# Qwiic_Featherwing.net
KiCad netlist of a schematic drawn in EAGLE
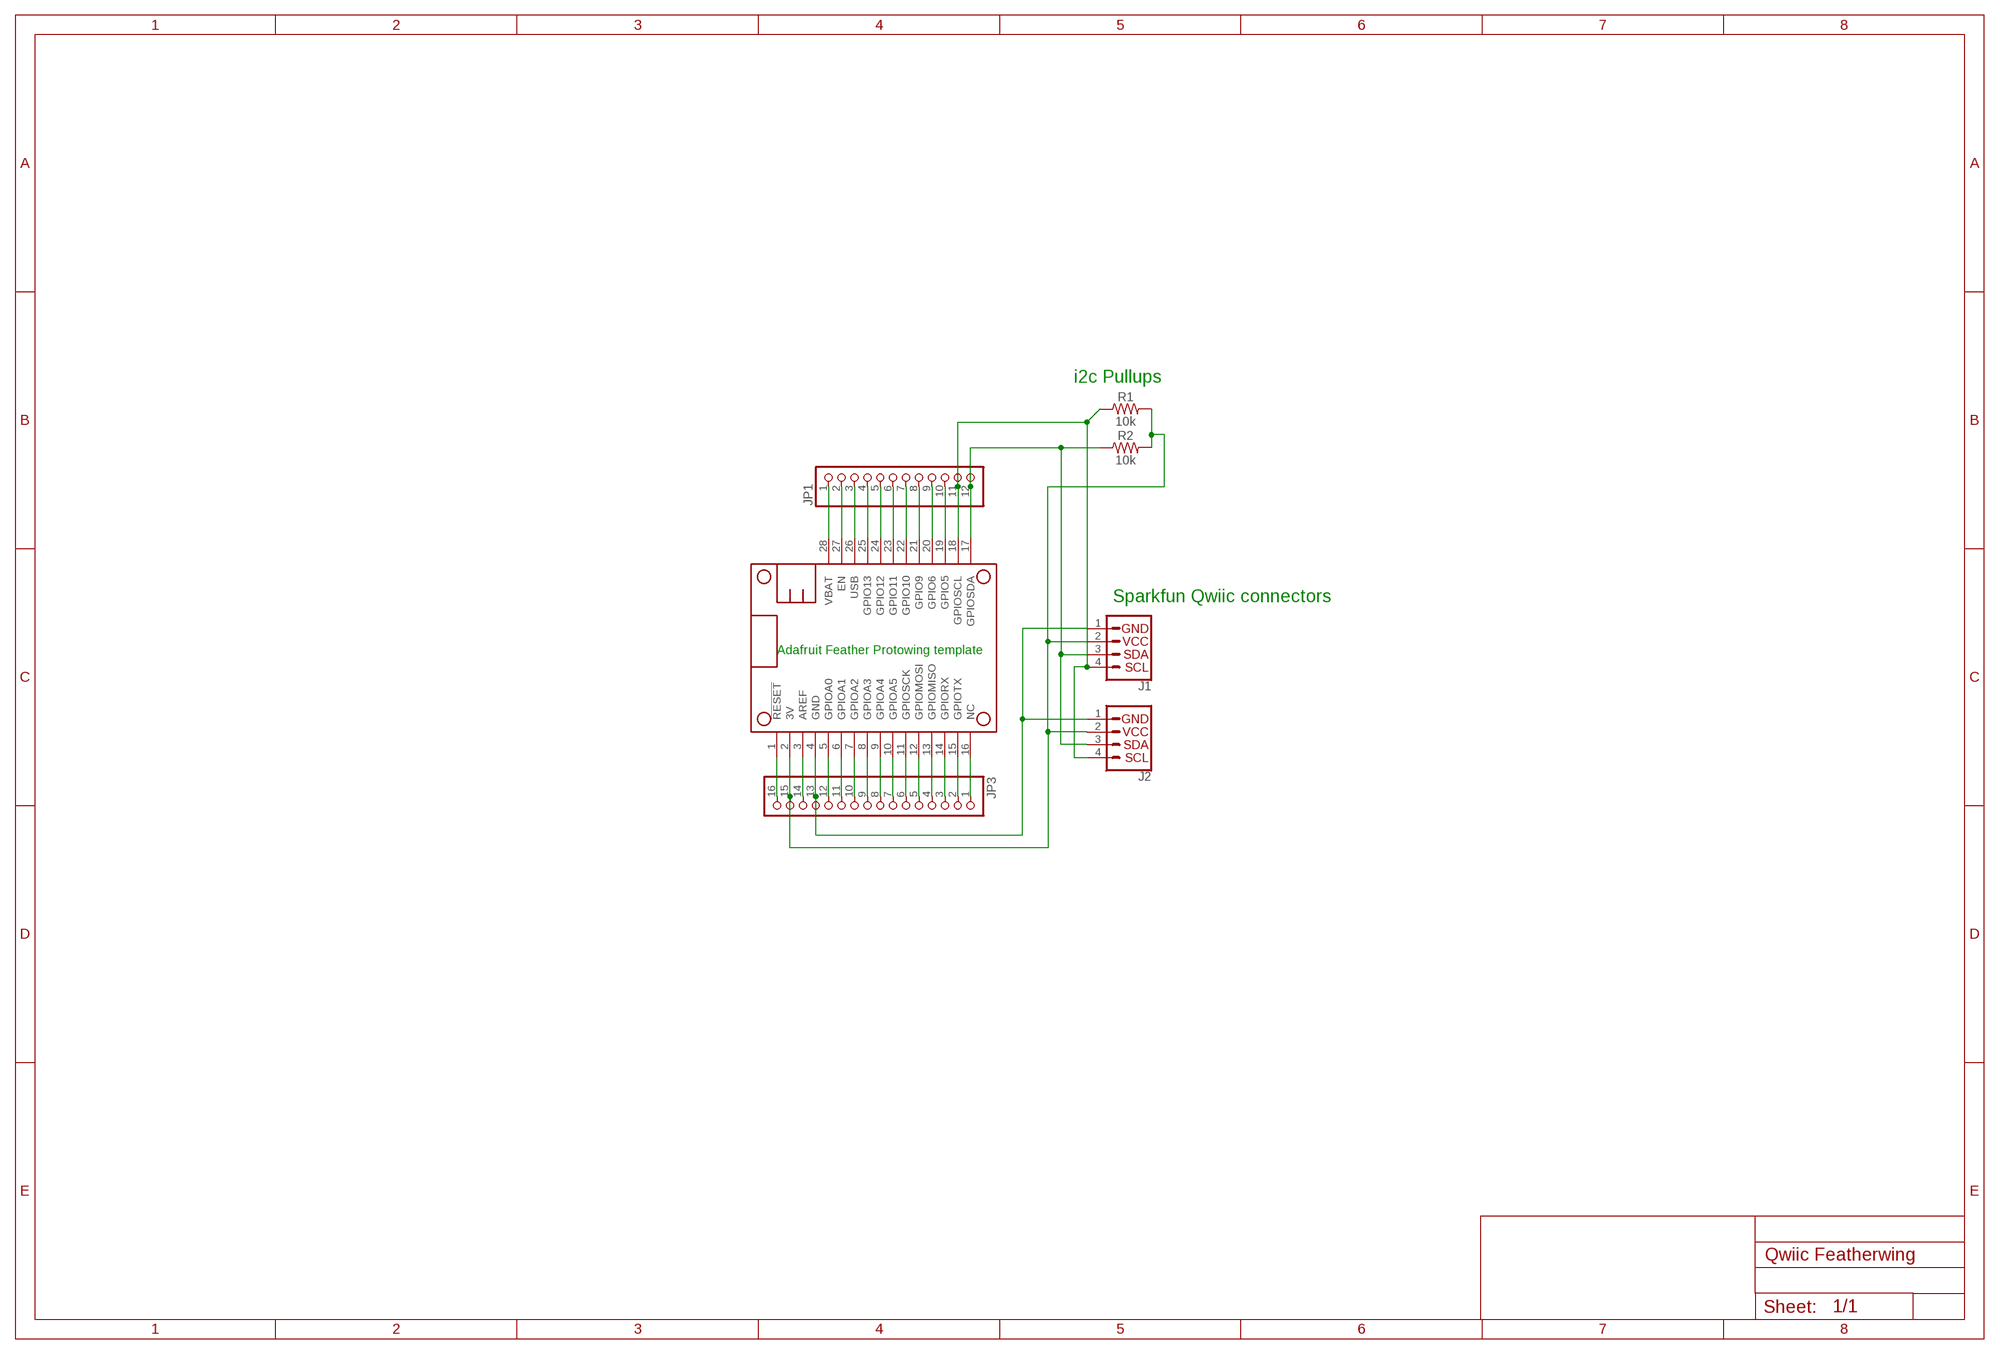
[diagram p0: schematic, sheet 1]

(export (version "E")
  (design (tool "Eeschema 10.0.6"))
  (components
    (comp (ref "J1")
      (value "QWIIC_CONNECTORJS-1MM")
      (footprint "eagle-import:1X04_1MM_RA")
      (libsource (lib "eagle-import") (part "QWIIC_CONNECTORJS-1MM"))
    )
    (comp (ref "J2")
      (value "QWIIC_CONNECTORJS-1MM")
      (footprint "eagle-import:1X04_1MM_RA")
      (libsource (lib "eagle-import") (part "QWIIC_CONNECTORJS-1MM"))
    )
    (comp (ref "JP1")
      (value "HEADER-1X1276MIL")
      (footprint "eagle-import:1X12_ROUND_76MIL")
      (libsource (lib "eagle-import") (part "HEADER-1X1276MIL"))
    )
    (comp (ref "JP3")
      (value "HEADER-1X16_76MIL")
      (footprint "eagle-import:1X16_ROUND_76MIL")
      (libsource (lib "eagle-import") (part "HEADER-1X16_76MIL"))
    )
    (comp (ref "MS1")
      (value "FEATHERWING")
      (footprint "eagle-import:FEATHERWING")
      (libsource (lib "eagle-import") (part "FEATHERWING"))
    )
    (comp (ref "R1")
      (value "10k")
      (footprint "eagle-import:0603")
      (libsource (lib "eagle-import") (part "10KOHM-0603-1/10W-1%"))
    )
    (comp (ref "R2")
      (value "10k")
      (footprint "eagle-import:0603")
      (libsource (lib "eagle-import") (part "10KOHM-0603-1/10W-1%"))
    )
  )
  (nets
    (net (code "1") (name "Net-(J1-GND)") (class "Default")
      (node (ref "J1") (pin "1") (pinfunction "GND_1") (pintype "power_in"))
      (node (ref "J2") (pin "1") (pinfunction "GND_1") (pintype "power_in"))
      (node (ref "JP3") (pin "13") (pinfunction "13_13") (pintype "passive"))
      (node (ref "MS1") (pin "4") (pinfunction "GND_4") (pintype "power_in"))
    )
    (net (code "2") (name "Net-(J1-SCL)") (class "Default")
      (node (ref "J1") (pin "4") (pinfunction "SCL_4") (pintype "passive"))
      (node (ref "J2") (pin "4") (pinfunction "SCL_4") (pintype "passive"))
      (node (ref "JP1") (pin "11") (pinfunction "11_11") (pintype "passive"))
      (node (ref "MS1") (pin "18") (pinfunction "GPIOSCL_18") (pintype "bidirectional"))
      (node (ref "R1") (pin "1") (pinfunction "1_1") (pintype "passive"))
    )
    (net (code "3") (name "Net-(J1-SDA)") (class "Default")
      (node (ref "J1") (pin "3") (pinfunction "SDA_3") (pintype "passive"))
      (node (ref "J2") (pin "3") (pinfunction "SDA_3") (pintype "passive"))
      (node (ref "JP1") (pin "12") (pinfunction "12_12") (pintype "passive"))
      (node (ref "MS1") (pin "17") (pinfunction "GPIOSDA_17") (pintype "bidirectional"))
      (node (ref "R2") (pin "1") (pinfunction "1_1") (pintype "passive"))
    )
    (net (code "4") (name "Net-(J1-VCC)") (class "Default")
      (node (ref "J1") (pin "2") (pinfunction "VCC_2") (pintype "power_in"))
      (node (ref "J2") (pin "2") (pinfunction "VCC_2") (pintype "power_in"))
      (node (ref "JP3") (pin "15") (pinfunction "15_15") (pintype "passive"))
      (node (ref "MS1") (pin "2") (pinfunction "3V_2") (pintype "power_in"))
      (node (ref "R1") (pin "2") (pinfunction "2_2") (pintype "passive"))
      (node (ref "R2") (pin "2") (pinfunction "2_2") (pintype "passive"))
    )
    (net (code "5") (name "Net-(MS1-AREF)") (class "Default")
      (node (ref "JP3") (pin "14") (pinfunction "14_14") (pintype "passive"))
      (node (ref "MS1") (pin "3") (pinfunction "AREF_3") (pintype "passive"))
    )
    (net (code "6") (name "Net-(MS1-EN)") (class "Default")
      (node (ref "JP1") (pin "2") (pinfunction "2_2") (pintype "passive"))
      (node (ref "MS1") (pin "27") (pinfunction "EN_27") (pintype "passive"))
    )
    (net (code "7") (name "Net-(MS1-GPIO5)") (class "Default")
      (node (ref "JP1") (pin "10") (pinfunction "10_10") (pintype "passive"))
      (node (ref "MS1") (pin "19") (pinfunction "GPIO5_19") (pintype "bidirectional"))
    )
    (net (code "8") (name "Net-(MS1-GPIO6)") (class "Default")
      (node (ref "JP1") (pin "9") (pinfunction "9_9") (pintype "passive"))
      (node (ref "MS1") (pin "20") (pinfunction "GPIO6_20") (pintype "bidirectional"))
    )
    (net (code "9") (name "Net-(MS1-GPIO9)") (class "Default")
      (node (ref "JP1") (pin "8") (pinfunction "8_8") (pintype "passive"))
      (node (ref "MS1") (pin "21") (pinfunction "GPIO9_21") (pintype "bidirectional"))
    )
    (net (code "10") (name "Net-(MS1-GPIO10)") (class "Default")
      (node (ref "JP1") (pin "7") (pinfunction "7_7") (pintype "passive"))
      (node (ref "MS1") (pin "22") (pinfunction "GPIO10_22") (pintype "bidirectional"))
    )
    (net (code "11") (name "Net-(MS1-GPIO11)") (class "Default")
      (node (ref "JP1") (pin "6") (pinfunction "6_6") (pintype "passive"))
      (node (ref "MS1") (pin "23") (pinfunction "GPIO11_23") (pintype "bidirectional"))
    )
    (net (code "12") (name "Net-(MS1-GPIO12)") (class "Default")
      (node (ref "JP1") (pin "5") (pinfunction "5_5") (pintype "passive"))
      (node (ref "MS1") (pin "24") (pinfunction "GPIO12_24") (pintype "bidirectional"))
    )
    (net (code "13") (name "Net-(MS1-GPIO13)") (class "Default")
      (node (ref "JP1") (pin "4") (pinfunction "4_4") (pintype "passive"))
      (node (ref "MS1") (pin "25") (pinfunction "GPIO13_25") (pintype "bidirectional"))
    )
    (net (code "14") (name "Net-(MS1-GPIOA0)") (class "Default")
      (node (ref "JP3") (pin "12") (pinfunction "12_12") (pintype "passive"))
      (node (ref "MS1") (pin "5") (pinfunction "GPIOA0_5") (pintype "bidirectional"))
    )
    (net (code "15") (name "Net-(MS1-GPIOA1)") (class "Default")
      (node (ref "JP3") (pin "11") (pinfunction "11_11") (pintype "passive"))
      (node (ref "MS1") (pin "6") (pinfunction "GPIOA1_6") (pintype "bidirectional"))
    )
    (net (code "16") (name "Net-(MS1-GPIOA2)") (class "Default")
      (node (ref "JP3") (pin "10") (pinfunction "10_10") (pintype "passive"))
      (node (ref "MS1") (pin "7") (pinfunction "GPIOA2_7") (pintype "bidirectional"))
    )
    (net (code "17") (name "Net-(MS1-GPIOA3)") (class "Default")
      (node (ref "JP3") (pin "9") (pinfunction "9_9") (pintype "passive"))
      (node (ref "MS1") (pin "8") (pinfunction "GPIOA3_8") (pintype "bidirectional"))
    )
    (net (code "18") (name "Net-(MS1-GPIOA4)") (class "Default")
      (node (ref "JP3") (pin "8") (pinfunction "8_8") (pintype "passive"))
      (node (ref "MS1") (pin "9") (pinfunction "GPIOA4_9") (pintype "bidirectional"))
    )
    (net (code "19") (name "Net-(MS1-GPIOA5)") (class "Default")
      (node (ref "JP3") (pin "7") (pinfunction "7_7") (pintype "passive"))
      (node (ref "MS1") (pin "10") (pinfunction "GPIOA5_10") (pintype "bidirectional"))
    )
    (net (code "20") (name "Net-(MS1-GPIOMISO)") (class "Default")
      (node (ref "JP3") (pin "4") (pinfunction "4_4") (pintype "passive"))
      (node (ref "MS1") (pin "13") (pinfunction "GPIOMISO_13") (pintype "bidirectional"))
    )
    (net (code "21") (name "Net-(MS1-GPIOMOSI)") (class "Default")
      (node (ref "JP3") (pin "5") (pinfunction "5_5") (pintype "passive"))
      (node (ref "MS1") (pin "12") (pinfunction "GPIOMOSI_12") (pintype "bidirectional"))
    )
    (net (code "22") (name "Net-(MS1-GPIORX)") (class "Default")
      (node (ref "JP3") (pin "3") (pinfunction "3_3") (pintype "passive"))
      (node (ref "MS1") (pin "14") (pinfunction "GPIORX_14") (pintype "bidirectional"))
    )
    (net (code "23") (name "Net-(MS1-GPIOSCK)") (class "Default")
      (node (ref "JP3") (pin "6") (pinfunction "6_6") (pintype "passive"))
      (node (ref "MS1") (pin "11") (pinfunction "GPIOSCK_11") (pintype "bidirectional"))
    )
    (net (code "24") (name "Net-(MS1-GPIOTX)") (class "Default")
      (node (ref "JP3") (pin "2") (pinfunction "2_2") (pintype "passive"))
      (node (ref "MS1") (pin "15") (pinfunction "GPIOTX_15") (pintype "bidirectional"))
    )
    (net (code "25") (name "Net-(MS1-NC)") (class "Default")
      (node (ref "JP3") (pin "1") (pinfunction "1_1") (pintype "passive"))
      (node (ref "MS1") (pin "16") (pinfunction "NC_16") (pintype "passive"))
    )
    (net (code "26") (name "Net-(MS1-USB)") (class "Default")
      (node (ref "JP1") (pin "3") (pinfunction "3_3") (pintype "passive"))
      (node (ref "MS1") (pin "26") (pinfunction "USB_26") (pintype "power_in"))
    )
    (net (code "27") (name "Net-(MS1-VBAT)") (class "Default")
      (node (ref "JP1") (pin "1") (pinfunction "1_1") (pintype "passive"))
      (node (ref "MS1") (pin "28") (pinfunction "VBAT_28") (pintype "power_in"))
    )
    (net (code "28") (name "Net-(MS1-~{RESET})") (class "Default")
      (node (ref "JP3") (pin "16") (pinfunction "16_16") (pintype "passive"))
      (node (ref "MS1") (pin "1") (pinfunction "~{RESET}_1") (pintype "input"))
    )
  )
)
